# Power.net
KiCad netlist of a schematic drawn in Altium Designer
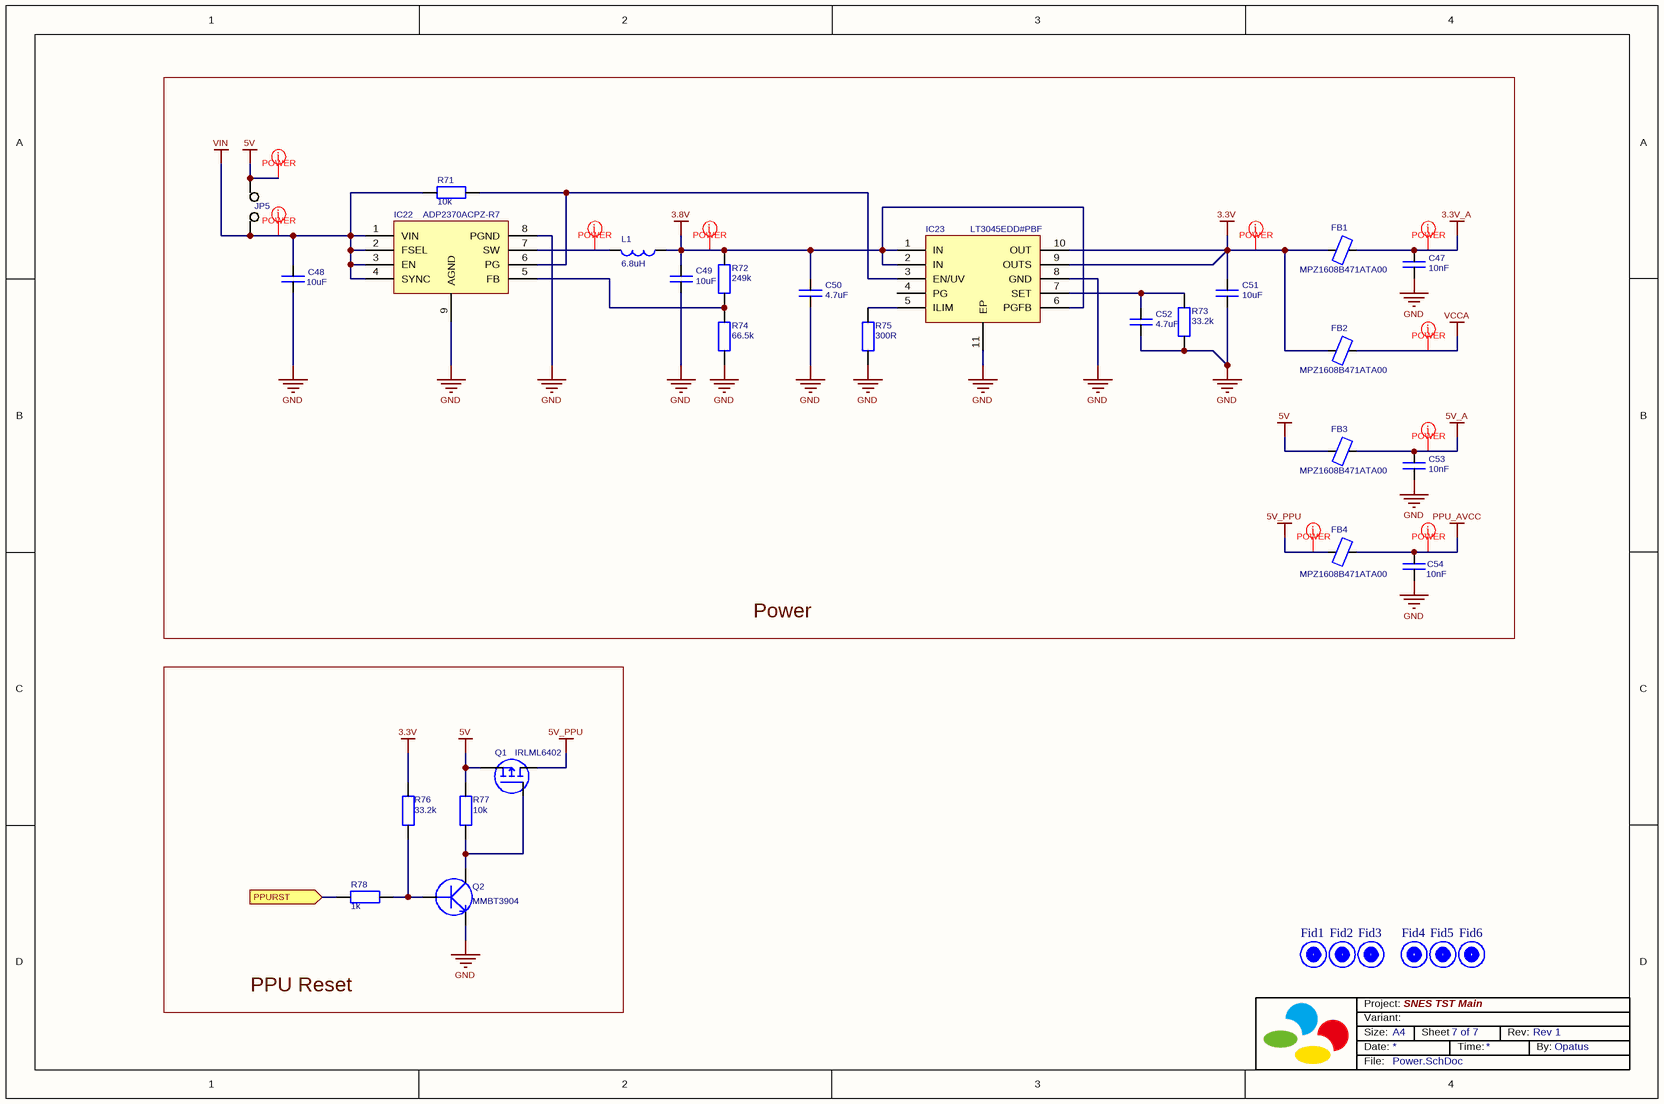
[diagram p0: Power.SchDoc]

(export (version "E")
  (design (tool "Eeschema 10.0.6"))
  (components
    (comp (ref "C47")
      (value "10nF")
      (footprint "Cap_0402_Chip")
      (fields
        (field (name "TOLERANCE") "±20%")
        (field (name "Comment") "Ceramic Capacitor 10nF 10V ±20% X7R 0402")
      )
      (libsource (lib "PCB") (part "Capacitor"))
    )
    (comp (ref "C48")
      (value "10uF")
      (footprint "Cap_0805_Chip")
      (fields
        (field (name "TOLERANCE") "±20%")
        (field (name "Comment") "Ceramic Capacitor 10uF 25V ±20% X5R 0805")
      )
      (libsource (lib "PCB") (part "Capacitor"))
    )
    (comp (ref "C49")
      (value "10uF")
      (footprint "Cap_0603_Chip")
      (fields
        (field (name "TOLERANCE") "±20%")
        (field (name "Comment") "Ceramic Capacitor 10uF 10V ±20% X5R 0603")
      )
      (libsource (lib "PCB") (part "Capacitor"))
    )
    (comp (ref "C50")
      (value "4.7uF")
      (footprint "Cap_0603_Chip")
      (fields
        (field (name "TOLERANCE") "±20%")
        (field (name "Comment") "Ceramic Capacitor 4.7uF 10V ±20% X5R 0603")
      )
      (libsource (lib "PCB") (part "Capacitor"))
    )
    (comp (ref "C51")
      (value "10uF")
      (footprint "Cap_0603_Chip")
      (fields
        (field (name "TOLERANCE") "±20%")
        (field (name "Comment") "Ceramic Capacitor 10uF 10V ±20% X5R 0603")
      )
      (libsource (lib "PCB") (part "Capacitor"))
    )
    (comp (ref "C52")
      (value "4.7uF")
      (footprint "Cap_0603_Chip")
      (fields
        (field (name "TOLERANCE") "±20%")
        (field (name "Comment") "Ceramic Capacitor 4.7uF 10V ±20% X5R 0603")
      )
      (libsource (lib "PCB") (part "Capacitor"))
    )
    (comp (ref "C53")
      (value "10nF")
      (footprint "Cap_0402_Chip")
      (fields
        (field (name "TOLERANCE") "±20%")
        (field (name "Comment") "Ceramic Capacitor 10nF 10V ±20% X7R 0402")
      )
      (libsource (lib "PCB") (part "Capacitor"))
    )
    (comp (ref "C54")
      (value "10nF")
      (footprint "Cap_0402_Chip")
      (fields
        (field (name "TOLERANCE") "±20%")
        (field (name "Comment") "Ceramic Capacitor 10nF 10V ±20% X7R 0402")
      )
      (libsource (lib "PCB") (part "Capacitor"))
    )
    (comp (ref "FB1")
      (value "470Ohm  1A")
      (footprint "Ind_0603_Chip")
      (fields
        (field (name "MANUFACTURER_PART_NUMBER") "MPZ1608B471ATA00")
        (field (name "MANUFACTURER") "TDK")
      )
      (libsource (lib "PCB") (part "Ferrite Bead"))
    )
    (comp (ref "FB2")
      (value "470Ohm  1A")
      (footprint "Ind_0603_Chip")
      (fields
        (field (name "MANUFACTURER_PART_NUMBER") "MPZ1608B471ATA00")
        (field (name "MANUFACTURER") "TDK")
      )
      (libsource (lib "PCB") (part "Ferrite Bead"))
    )
    (comp (ref "FB3")
      (value "470Ohm  1A")
      (footprint "Ind_0603_Chip")
      (fields
        (field (name "MANUFACTURER_PART_NUMBER") "MPZ1608B471ATA00")
        (field (name "MANUFACTURER") "TDK")
      )
      (libsource (lib "PCB") (part "Ferrite Bead"))
    )
    (comp (ref "FB4")
      (value "470Ohm  1A")
      (footprint "Ind_0603_Chip")
      (fields
        (field (name "MANUFACTURER_PART_NUMBER") "MPZ1608B471ATA00")
        (field (name "MANUFACTURER") "TDK")
      )
      (libsource (lib "PCB") (part "Ferrite Bead"))
    )
    (comp (ref "Fid1")
      (value "Fiducial")
      (footprint "Fiducial_1_side")
      (libsource (lib "PCB") (part "Fiducial"))
    )
    (comp (ref "Fid2")
      (value "Fiducial")
      (footprint "Fiducial_1_side")
      (libsource (lib "PCB") (part "Fiducial"))
    )
    (comp (ref "Fid3")
      (value "Fiducial")
      (footprint "Fiducial_1_side")
      (libsource (lib "PCB") (part "Fiducial"))
    )
    (comp (ref "Fid4")
      (value "Fiducial")
      (footprint "Fiducial_1_side")
      (libsource (lib "PCB") (part "Fiducial"))
    )
    (comp (ref "Fid5")
      (value "Fiducial")
      (footprint "Fiducial_1_side")
      (libsource (lib "PCB") (part "Fiducial"))
    )
    (comp (ref "Fid6")
      (value "Fiducial")
      (footprint "Fiducial_1_side")
      (libsource (lib "PCB") (part "Fiducial"))
    )
    (comp (ref "IC22")
      (value "ADP2370")
      (footprint "LFCSP8")
      (description "SMPS")
      (fields
        (field (name "MANUFACTURER") "Analog Devices Inc")
        (field (name "MANUFACTURER_PART_NUMBER") "ADP2370ACPZ-R7")
      )
      (libsource (lib "PCB") (part "ADP2370"))
    )
    (comp (ref "IC23")
      (value "LT3045")
      (footprint "DFN10")
      (description "LDO")
      (fields
        (field (name "MANUFACTURER") "Analog Devices Inc")
        (field (name "MANUFACTURER_PART_NUMBER") "LT3045EDD#PBF")
      )
      (libsource (lib "PCB") (part "LT3045"))
    )
    (comp (ref "JP5") (value "Jumper") (footprint "Jumper Big") (libsource (lib "PCB") (part "Jumper")))
    (comp (ref "L1")
      (value "6.8uH")
      (footprint "WE-MAPI_3020")
      (fields
        (field (name "MANUFACTURER") "Würth")
        (field (name "MANUFACTURER_PART_NUMBER") "74438336068")
        (field (name "Comment") "0603")
      )
      (libsource (lib "PCB") (part "L"))
    )
    (comp (ref "Q1")
      (value "IRLML6402")
      (footprint "SOT23_FET")
      (fields (field (name "MANUFACTURER") "Diodes"))
      (libsource (lib "PCB") (part "Mosfet1"))
    )
    (comp (ref "Q2")
      (value "MMBT3904")
      (footprint "SOT23_Transistor")
      (fields (field (name "MANUFACTURER") "Diodes"))
      (libsource (lib "PCB") (part "T_NPN"))
    )
    (comp (ref "R71")
      (value "10k")
      (footprint "Res_0402_Chip")
      (fields (field (name "TOLERANCE") "±1%") (field (name "Comment") "Resistor 10k 0402 ±1%"))
      (libsource (lib "PCB") (part "R"))
    )
    (comp (ref "R72")
      (value "249k")
      (footprint "Res_0402_Chip")
      (fields (field (name "TOLERANCE") "±1%") (field (name "Comment") "Resistor 249k 0402 ±1%"))
      (libsource (lib "") (part "R_1"))
    )
    (comp (ref "R73")
      (value "33.2k")
      (footprint "Res_0402_Chip")
      (fields (field (name "TOLERANCE") "±1%") (field (name "Comment") "Resistor 33.2k 0402 ±1%"))
      (libsource (lib "") (part "R_1"))
    )
    (comp (ref "R74")
      (value "66.5k")
      (footprint "Res_0402_Chip")
      (fields (field (name "TOLERANCE") "±1%") (field (name "Comment") "Resistor 66.5k 0402 ±1%"))
      (libsource (lib "") (part "R_1"))
    )
    (comp (ref "R75")
      (value "300R")
      (footprint "Res_0402_Chip")
      (fields (field (name "TOLERANCE") "±1%") (field (name "Comment") "Resistor 300R 0402 ±1%"))
      (libsource (lib "") (part "R_1"))
    )
    (comp (ref "R76")
      (value "33.2k")
      (footprint "Res_0402_Chip")
      (fields (field (name "TOLERANCE") "±1%") (field (name "Comment") "Resistor 33.2k 0402 ±1%"))
      (libsource (lib "") (part "R_2"))
    )
    (comp (ref "R77")
      (value "10k")
      (footprint "Res_0402_Chip")
      (fields (field (name "TOLERANCE") "±1%") (field (name "Comment") "Resistor 10k 0402 ±1%"))
      (libsource (lib "") (part "R_1"))
    )
    (comp (ref "R78")
      (value "1k")
      (footprint "Res_0402_Chip")
      (fields (field (name "TOLERANCE") "±1%") (field (name "Comment") "Resistor 1k 0402 ±1%"))
      (libsource (lib "PCB") (part "R"))
    )
  )
  (nets
    (net (code "1") (name "/PPURST") (class "Default") (node (ref "R78") (pin "1") (pintype "passive")))
    (net (code "2") (name "3.3V") (class "Default")
      (node (ref "C51") (pin "2") (pintype "passive"))
      (node (ref "FB1") (pin "1") (pintype "passive"))
      (node (ref "FB2") (pin "1") (pintype "passive"))
      (node (ref "IC23") (pin "10") (pinfunction "OUT_10") (pintype "power_in"))
      (node (ref "IC23") (pin "9") (pinfunction "OUTS_9") (pintype "power_in"))
      (node (ref "R76") (pin "2") (pintype "passive"))
    )
    (net (code "3") (name "3.3V_A") (class "Default")
      (node (ref "C47") (pin "1") (pintype "passive"))
      (node (ref "FB1") (pin "2") (pintype "passive"))
    )
    (net (code "4") (name "3.8V") (class "Default")
      (node (ref "C49") (pin "2") (pintype "passive"))
      (node (ref "C50") (pin "2") (pintype "passive"))
      (node (ref "IC23") (pin "1") (pinfunction "IN_1") (pintype "power_in"))
      (node (ref "IC23") (pin "2") (pinfunction "IN_2") (pintype "power_in"))
      (node (ref "IC23") (pin "6") (pinfunction "PGFB_6") (pintype "power_in"))
      (node (ref "L1") (pin "2") (pintype "passive"))
      (node (ref "R72") (pin "1") (pintype "passive"))
    )
    (net (code "5") (name "5V") (class "Default")
      (node (ref "FB3") (pin "1") (pintype "passive"))
      (node (ref "JP5") (pin "1") (pinfunction "0_1") (pintype "passive"))
      (node (ref "Q1") (pin "S") (pinfunction "S_S") (pintype "passive"))
      (node (ref "R77") (pin "1") (pintype "passive"))
    )
    (net (code "6") (name "5V_A") (class "Default")
      (node (ref "C53") (pin "1") (pintype "passive"))
      (node (ref "FB3") (pin "2") (pintype "passive"))
    )
    (net (code "7") (name "5V_PPU") (class "Default")
      (node (ref "FB4") (pin "1") (pintype "passive"))
      (node (ref "Q1") (pin "D") (pinfunction "D_D") (pintype "passive"))
    )
    (net (code "8") (name "GND") (class "Default")
      (node (ref "C47") (pin "2") (pintype "passive"))
      (node (ref "C48") (pin "1") (pintype "passive"))
      (node (ref "C49") (pin "1") (pintype "passive"))
      (node (ref "C50") (pin "1") (pintype "passive"))
      (node (ref "C51") (pin "1") (pintype "passive"))
      (node (ref "C52") (pin "1") (pintype "passive"))
      (node (ref "C53") (pin "2") (pintype "passive"))
      (node (ref "C54") (pin "2") (pintype "passive"))
      (node (ref "IC22") (pin "8") (pinfunction "PGND_8") (pintype "power_in"))
      (node (ref "IC22") (pin "9") (pinfunction "AGND_9") (pintype "power_in"))
      (node (ref "IC23") (pin "11") (pinfunction "EP_11") (pintype "power_in"))
      (node (ref "IC23") (pin "8") (pinfunction "GND_8") (pintype "power_in"))
      (node (ref "Q2") (pin "E") (pinfunction "E_E") (pintype "passive"))
      (node (ref "R73") (pin "2") (pintype "passive"))
      (node (ref "R74") (pin "2") (pintype "passive"))
      (node (ref "R75") (pin "2") (pintype "passive"))
    )
    (net (code "9") (name "Net-(IC22-FB)") (class "Default")
      (node (ref "IC22") (pin "5") (pinfunction "FB_5") (pintype "power_in"))
      (node (ref "R72") (pin "2") (pintype "passive"))
      (node (ref "R74") (pin "1") (pintype "passive"))
    )
    (net (code "10") (name "Net-(IC22-PG)") (class "Default")
      (node (ref "IC22") (pin "6") (pinfunction "PG_6") (pintype "power_in"))
      (node (ref "IC23") (pin "3") (pinfunction "EN/UV_3") (pintype "power_in"))
      (node (ref "R71") (pin "2") (pintype "passive"))
    )
    (net (code "11") (name "Net-(IC22-SW)") (class "Default")
      (node (ref "IC22") (pin "7") (pinfunction "SW_7") (pintype "power_in"))
      (node (ref "L1") (pin "1") (pintype "passive"))
    )
    (net (code "12") (name "Net-(IC23-ILIM)") (class "Default")
      (node (ref "IC23") (pin "5") (pinfunction "ILIM_5") (pintype "power_in"))
      (node (ref "R75") (pin "1") (pintype "passive"))
    )
    (net (code "13") (name "Net-(IC23-SET)") (class "Default")
      (node (ref "C52") (pin "2") (pintype "passive"))
      (node (ref "IC23") (pin "7") (pinfunction "SET_7") (pintype "power_in"))
      (node (ref "R73") (pin "1") (pintype "passive"))
    )
    (net (code "14") (name "Net-(Q1-PadG)") (class "Default")
      (node (ref "Q1") (pin "G") (pinfunction "G_G") (pintype "passive"))
      (node (ref "Q2") (pin "C") (pinfunction "C_C") (pintype "passive"))
      (node (ref "R77") (pin "2") (pintype "passive"))
    )
    (net (code "15") (name "Net-(Q2-PadB)") (class "Default")
      (node (ref "Q2") (pin "B") (pinfunction "B_B") (pintype "passive"))
      (node (ref "R76") (pin "1") (pintype "passive"))
      (node (ref "R78") (pin "2") (pintype "passive"))
    )
    (net (code "16") (name "PPU_AVCC") (class "Default")
      (node (ref "C54") (pin "1") (pintype "passive"))
      (node (ref "FB4") (pin "2") (pintype "passive"))
    )
    (net (code "17") (name "VCCA") (class "Default") (node (ref "FB2") (pin "2") (pintype "passive")))
    (net (code "18") (name "VIN") (class "Default")
      (node (ref "C48") (pin "2") (pintype "passive"))
      (node (ref "IC22") (pin "1") (pinfunction "VIN_1") (pintype "power_in"))
      (node (ref "IC22") (pin "2") (pinfunction "FSEL_2") (pintype "power_in"))
      (node (ref "IC22") (pin "3") (pinfunction "EN_3") (pintype "power_in"))
      (node (ref "IC22") (pin "4") (pinfunction "SYNC_4") (pintype "power_in"))
      (node (ref "JP5") (pin "2") (pinfunction "0_2") (pintype "passive"))
      (node (ref "R71") (pin "1") (pintype "passive"))
    )
    (net (code "19") (name "unconnected-(IC23-PG-Pad4)") (class "Default")
      (node (ref "IC23") (pin "4") (pinfunction "PG_4") (pintype "power_in"))
    )
  )
)
